# hdmi_block.net
KiCad netlist of a schematic drawn in Altium Designer
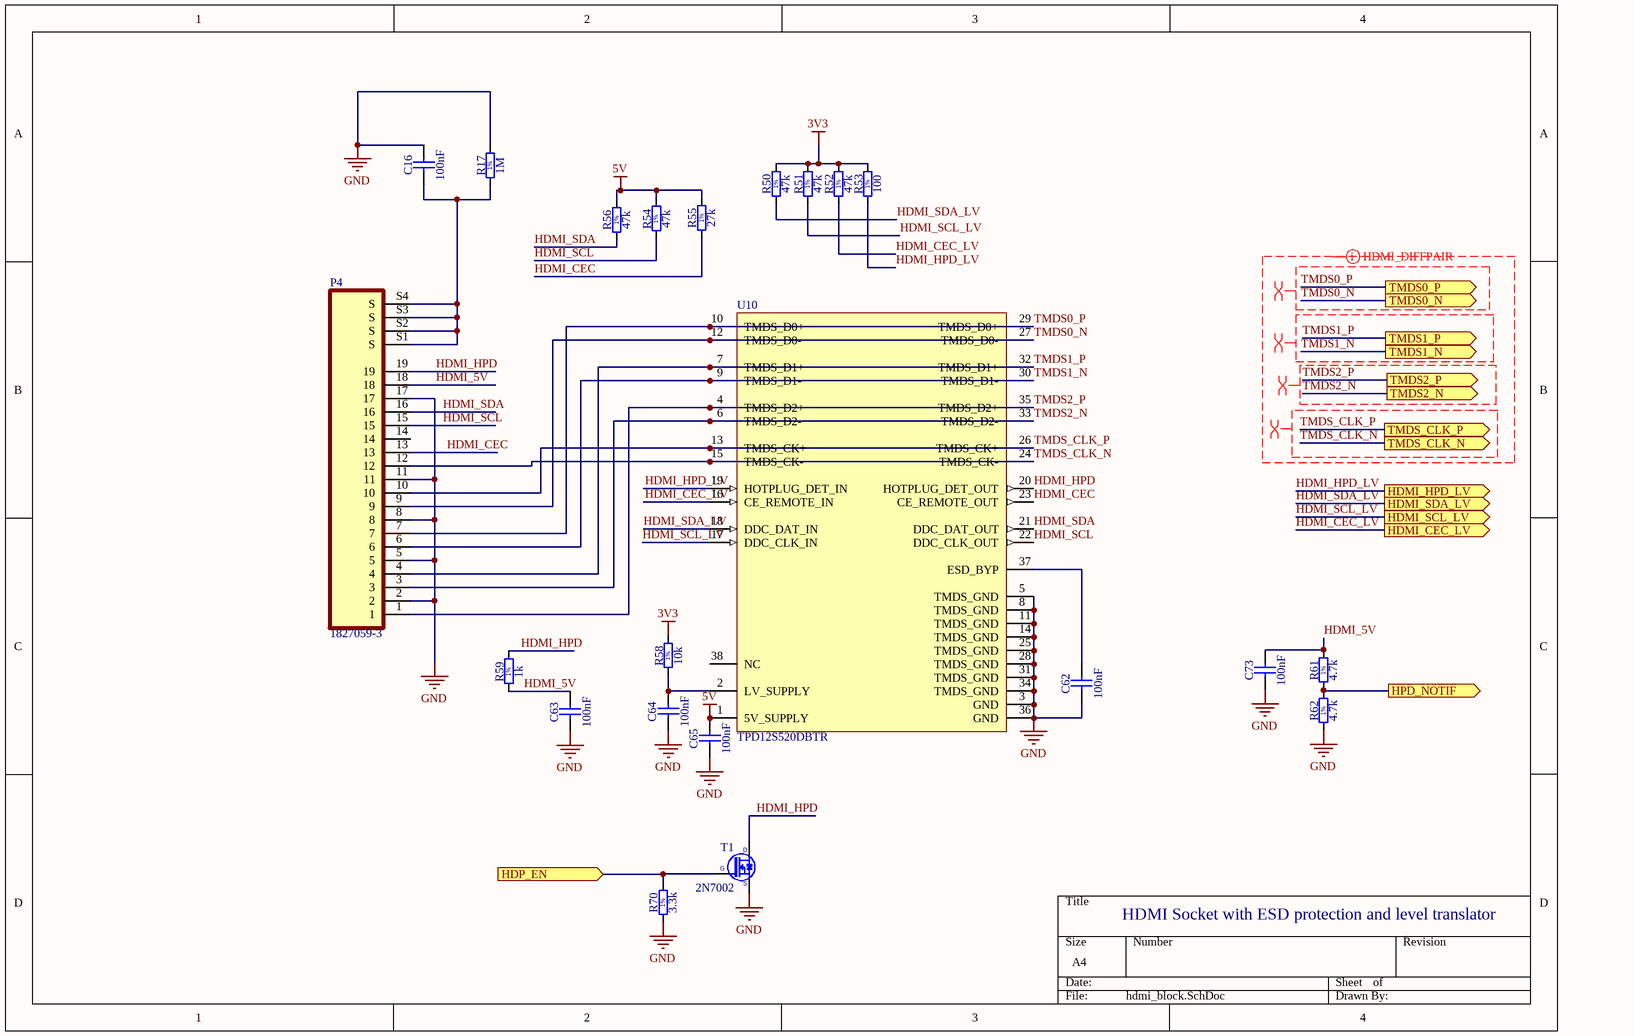
[diagram p0: hdmi_block.SchDoc]

(export (version "E")
  (design (tool "Eeschema 10.0.6"))
  (components
    (comp (ref "C16")
      (value "100nF")
      (footprint "CAPC2013X100N")
      (description "Non-polarised capacitor")
      (fields
        (field (name "PART NUMBER") "CC0805_1.5NF_50V_5%_C0G")
        (field (name "VOLTAGE") "50V")
        (field (name "AUTHOR") "CERN DEM BC")
      )
      (libsource (lib "Capacitors") (part "Capacitor - non polarized"))
    )
    (comp (ref "C62")
      (value "100nF")
      (footprint "CAPC2013X100N")
      (description "Non-polarised capacitor")
      (fields
        (field (name "PART NUMBER") "CC0805_1.5NF_50V_5%_C0G")
        (field (name "VOLTAGE") "50V")
        (field (name "AUTHOR") "CERN DEM BC")
      )
      (libsource (lib "Capacitors") (part "Capacitor - non polarized"))
    )
    (comp (ref "C63")
      (value "100nF")
      (footprint "CAPC2013X100N")
      (description "Non-polarised capacitor")
      (fields
        (field (name "PART NUMBER") "CC0805_1.5NF_50V_5%_C0G")
        (field (name "VOLTAGE") "50V")
        (field (name "AUTHOR") "CERN DEM BC")
      )
      (libsource (lib "Capacitors") (part "Capacitor - non polarized"))
    )
    (comp (ref "C64")
      (value "100nF")
      (footprint "CAPC2013X100N")
      (description "Non-polarised capacitor")
      (fields
        (field (name "PART NUMBER") "CC0805_1.5NF_50V_5%_C0G")
        (field (name "VOLTAGE") "50V")
        (field (name "AUTHOR") "CERN DEM BC")
      )
      (libsource (lib "Capacitors") (part "Capacitor - non polarized"))
    )
    (comp (ref "C65")
      (value "100nF")
      (footprint "CAPC2013X100N")
      (description "Non-polarised capacitor")
      (fields
        (field (name "PART NUMBER") "CC0805_1.5NF_50V_5%_C0G")
        (field (name "VOLTAGE") "50V")
        (field (name "AUTHOR") "CERN DEM BC")
      )
      (libsource (lib "Capacitors") (part "Capacitor - non polarized"))
    )
    (comp (ref "C73")
      (value "100nF")
      (footprint "CAPC2013X100N")
      (description "Non-polarised capacitor")
      (fields
        (field (name "PART NUMBER") "CC0805_1.5NF_50V_5%_C0G")
        (field (name "VOLTAGE") "50V")
        (field (name "AUTHOR") "CERN DEM BC")
      )
      (libsource (lib "Capacitors") (part "Capacitor - non polarized"))
    )
    (comp (ref "P4")
      (value "1827059-3")
      (footprint "TE_1827059-3")
      (description "EMBOSS PACKAGE HDMI CONN SMT NO-FLANGE T")
      (fields (field (name "MF") "TE Connectivity"))
      (libsource (lib "hdmi_conn_1827059-3") (part "1827059-3"))
    )
    (comp (ref "R17")
      (value "1M")
      (footprint "RESC1608X55N")
      (description "Resistor - 1%")
      (fields
        (field (name "PART NUMBER") "R0603_100K_1%_0.1W_100PPM")
        (field (name "POWER") "0.1W")
        (field (name "AUTHOR") "CERN DEM JLC")
      )
      (libsource (lib "Resistors") (part "Resistor - 1%"))
    )
    (comp (ref "R50")
      (value "47k")
      (footprint "RESC1608X55N")
      (description "Resistor - 1%")
      (fields
        (field (name "PART NUMBER") "R0603_100K_1%_0.1W_100PPM")
        (field (name "POWER") "0.1W")
        (field (name "AUTHOR") "CERN DEM JLC")
      )
      (libsource (lib "Resistors") (part "Resistor - 1%"))
    )
    (comp (ref "R51")
      (value "47k")
      (footprint "RESC1608X55N")
      (description "Resistor - 1%")
      (fields
        (field (name "PART NUMBER") "R0603_100K_1%_0.1W_100PPM")
        (field (name "POWER") "0.1W")
        (field (name "AUTHOR") "CERN DEM JLC")
      )
      (libsource (lib "Resistors") (part "Resistor - 1%"))
    )
    (comp (ref "R52")
      (value "47k")
      (footprint "RESC1608X55N")
      (description "Resistor - 1%")
      (fields
        (field (name "PART NUMBER") "R0603_100K_1%_0.1W_100PPM")
        (field (name "POWER") "0.1W")
        (field (name "AUTHOR") "CERN DEM JLC")
      )
      (libsource (lib "Resistors") (part "Resistor - 1%"))
    )
    (comp (ref "R53")
      (value "100")
      (footprint "RESC1608X55N")
      (description "Resistor - 1%")
      (fields
        (field (name "PART NUMBER") "R0603_100K_1%_0.1W_100PPM")
        (field (name "POWER") "0.1W")
        (field (name "AUTHOR") "CERN DEM JLC")
      )
      (libsource (lib "Resistors") (part "Resistor - 1%"))
    )
    (comp (ref "R54")
      (value "47k")
      (footprint "RESC1608X55N")
      (description "Resistor - 1%")
      (fields
        (field (name "PART NUMBER") "R0603_100K_1%_0.1W_100PPM")
        (field (name "POWER") "0.1W")
        (field (name "AUTHOR") "CERN DEM JLC")
      )
      (libsource (lib "Resistors") (part "Resistor - 1%"))
    )
    (comp (ref "R55")
      (value "27k")
      (footprint "RESC1608X55N")
      (description "Resistor - 1%")
      (fields
        (field (name "PART NUMBER") "R0603_100K_1%_0.1W_100PPM")
        (field (name "POWER") "0.1W")
        (field (name "AUTHOR") "CERN DEM JLC")
      )
      (libsource (lib "Resistors") (part "Resistor - 1%"))
    )
    (comp (ref "R56")
      (value "47k")
      (footprint "RESC1608X55N")
      (description "Resistor - 1%")
      (fields
        (field (name "PART NUMBER") "R0603_100K_1%_0.1W_100PPM")
        (field (name "POWER") "0.1W")
        (field (name "AUTHOR") "CERN DEM JLC")
      )
      (libsource (lib "Resistors") (part "Resistor - 1%"))
    )
    (comp (ref "R58")
      (value "10k")
      (footprint "RESC1608X55N")
      (description "Resistor - 1%")
      (fields
        (field (name "PART NUMBER") "R0603_100K_1%_0.1W_100PPM")
        (field (name "POWER") "0.1W")
        (field (name "AUTHOR") "CERN DEM JLC")
      )
      (libsource (lib "Resistors") (part "Resistor - 1%"))
    )
    (comp (ref "R59")
      (value "1k")
      (footprint "RESC1608X55N")
      (description "Resistor - 1%")
      (fields
        (field (name "PART NUMBER") "R0603_100K_1%_0.1W_100PPM")
        (field (name "POWER") "0.1W")
        (field (name "AUTHOR") "CERN DEM JLC")
      )
      (libsource (lib "Resistors") (part "Resistor - 1%"))
    )
    (comp (ref "R61")
      (value "4.7k")
      (footprint "RESC1608X55N")
      (description "Resistor - 1%")
      (fields
        (field (name "PART NUMBER") "R0603_100K_1%_0.1W_100PPM")
        (field (name "POWER") "0.1W")
        (field (name "AUTHOR") "CERN DEM JLC")
      )
      (libsource (lib "Resistors") (part "Resistor - 1%"))
    )
    (comp (ref "R62")
      (value "4.7k")
      (footprint "RESC1608X55N")
      (description "Resistor - 1%")
      (fields
        (field (name "PART NUMBER") "R0603_100K_1%_0.1W_100PPM")
        (field (name "POWER") "0.1W")
        (field (name "AUTHOR") "CERN DEM JLC")
      )
      (libsource (lib "Resistors") (part "Resistor - 1%"))
    )
    (comp (ref "R70")
      (value "3.3k")
      (footprint "RESC1608X55N")
      (description "Resistor - 1%")
      (fields
        (field (name "PART NUMBER") "R0603_100K_1%_0.1W_100PPM")
        (field (name "POWER") "0.1W")
        (field (name "AUTHOR") "CERN DEM JLC")
      )
      (libsource (lib "Resistors") (part "Resistor - 1%"))
    )
    (comp (ref "T1")
      (value "2N7002")
      (footprint "SOT95P240X130-3N")
      (description "N-CHANNEL MOSFET WITH DIODE")
      (fields (field (name "MANUFACTURER") "FAIRCHILD SEMICONDUCTOR") (field (name "AUTHOR") "CERN DEM JLC"))
      (libsource (lib "ICs And Semiconductors") (part "N-MOSFET-D 1G 2S 3D"))
    )
    (comp (ref "U10")
      (value "TPD12S520DBTR")
      (footprint "DBT38_L")
      (fields (field (name "MANUFACTURER") "Texas Instruments"))
      (libsource (lib "TI Interface ESD EMI Protection") (part "TPD12S520DBTR"))
    )
  )
  (nets
    (net (code "1") (name "/HDMI_5V") (class "Default")
      (node (ref "C63") (pin "2") (pinfunction "2_2") (pintype "passive"))
      (node (ref "C73") (pin "2") (pinfunction "2_2") (pintype "passive"))
      (node (ref "P4") (pin "18") (pinfunction "18_18") (pintype "passive"))
      (node (ref "R59") (pin "1") (pinfunction "1_1") (pintype "passive"))
      (node (ref "R61") (pin "2") (pinfunction "2_2") (pintype "passive"))
    )
    (net (code "2") (name "/HDMI_CEC") (class "Default")
      (node (ref "P4") (pin "13") (pinfunction "13_13") (pintype "passive"))
      (node (ref "R55") (pin "1") (pinfunction "1_1") (pintype "passive"))
      (node (ref "U10") (pin "23") (pinfunction "CE_REMOTE_OUT_23") (pintype "output"))
    )
    (net (code "3") (name "/HDMI_CEC_LV") (class "Default")
      (node (ref "R52") (pin "1") (pinfunction "1_1") (pintype "passive"))
      (node (ref "U10") (pin "16") (pinfunction "CE_REMOTE_IN_16") (pintype "input"))
    )
    (net (code "4") (name "/HDMI_HPD") (class "Default")
      (node (ref "P4") (pin "19") (pinfunction "19_19") (pintype "passive"))
      (node (ref "R59") (pin "2") (pinfunction "2_2") (pintype "passive"))
      (node (ref "T1") (pin "3") (pinfunction "D_3") (pintype "passive"))
      (node (ref "U10") (pin "20") (pinfunction "HOTPLUG_DET_OUT_20") (pintype "output"))
    )
    (net (code "5") (name "/HDMI_HPD_LV") (class "Default")
      (node (ref "R53") (pin "1") (pinfunction "1_1") (pintype "passive"))
      (node (ref "U10") (pin "19") (pinfunction "HOTPLUG_DET_IN_19") (pintype "input"))
    )
    (net (code "6") (name "/HDMI_SCL") (class "Default")
      (node (ref "P4") (pin "15") (pinfunction "15_15") (pintype "passive"))
      (node (ref "R54") (pin "1") (pinfunction "1_1") (pintype "passive"))
      (node (ref "U10") (pin "22") (pinfunction "DDC_CLK_OUT_22") (pintype "output"))
    )
    (net (code "7") (name "/HDMI_SCL_LV") (class "Default")
      (node (ref "R51") (pin "1") (pinfunction "1_1") (pintype "passive"))
      (node (ref "U10") (pin "17") (pinfunction "DDC_CLK_IN_17") (pintype "input"))
    )
    (net (code "8") (name "/HDMI_SDA") (class "Default")
      (node (ref "P4") (pin "16") (pinfunction "16_16") (pintype "passive"))
      (node (ref "R56") (pin "1") (pinfunction "1_1") (pintype "passive"))
      (node (ref "U10") (pin "21") (pinfunction "DDC_DAT_OUT_21") (pintype "output"))
    )
    (net (code "9") (name "/HDMI_SDA_LV") (class "Default")
      (node (ref "R50") (pin "1") (pinfunction "1_1") (pintype "passive"))
      (node (ref "U10") (pin "18") (pinfunction "DDC_DAT_IN_18") (pintype "input"))
    )
    (net (code "10") (name "/HDP_EN") (class "Default")
      (node (ref "R70") (pin "2") (pinfunction "2_2") (pintype "passive"))
      (node (ref "T1") (pin "1") (pinfunction "G_1") (pintype "passive"))
    )
    (net (code "11") (name "/HPD_NOTIF") (class "Default")
      (node (ref "R61") (pin "1") (pinfunction "1_1") (pintype "passive"))
      (node (ref "R62") (pin "2") (pinfunction "2_2") (pintype "passive"))
    )
    (net (code "12") (name "/TMDS0_N") (class "Default")
      (node (ref "P4") (pin "9") (pinfunction "9_9") (pintype "passive"))
      (node (ref "U10") (pin "12") (pinfunction "TMDS_D0-_12") (pintype "passive"))
      (node (ref "U10") (pin "27") (pinfunction "TMDS_D0-_27") (pintype "passive"))
    )
    (net (code "13") (name "/TMDS0_P") (class "Default")
      (node (ref "P4") (pin "7") (pinfunction "7_7") (pintype "passive"))
      (node (ref "U10") (pin "10") (pinfunction "TMDS_D0+_10") (pintype "passive"))
      (node (ref "U10") (pin "29") (pinfunction "TMDS_D0+_29") (pintype "passive"))
    )
    (net (code "14") (name "/TMDS1_N") (class "Default")
      (node (ref "P4") (pin "6") (pinfunction "6_6") (pintype "passive"))
      (node (ref "U10") (pin "30") (pinfunction "TMDS_D1-_30") (pintype "passive"))
      (node (ref "U10") (pin "9") (pinfunction "TMDS_D1-_9") (pintype "passive"))
    )
    (net (code "15") (name "/TMDS1_P") (class "Default")
      (node (ref "P4") (pin "4") (pinfunction "4_4") (pintype "passive"))
      (node (ref "U10") (pin "32") (pinfunction "TMDS_D1+_32") (pintype "passive"))
      (node (ref "U10") (pin "7") (pinfunction "TMDS_D1+_7") (pintype "passive"))
    )
    (net (code "16") (name "/TMDS2_N") (class "Default")
      (node (ref "P4") (pin "3") (pinfunction "3_3") (pintype "passive"))
      (node (ref "U10") (pin "33") (pinfunction "TMDS_D2-_33") (pintype "passive"))
      (node (ref "U10") (pin "6") (pinfunction "TMDS_D2-_6") (pintype "passive"))
    )
    (net (code "17") (name "/TMDS2_P") (class "Default")
      (node (ref "P4") (pin "1") (pinfunction "1_1") (pintype "passive"))
      (node (ref "U10") (pin "35") (pinfunction "TMDS_D2+_35") (pintype "passive"))
      (node (ref "U10") (pin "4") (pinfunction "TMDS_D2+_4") (pintype "passive"))
    )
    (net (code "18") (name "/TMDS_CLK_N") (class "Default")
      (node (ref "P4") (pin "12") (pinfunction "12_12") (pintype "passive"))
      (node (ref "U10") (pin "15") (pinfunction "TMDS_CK-_15") (pintype "passive"))
      (node (ref "U10") (pin "24") (pinfunction "TMDS_CK-_24") (pintype "passive"))
    )
    (net (code "19") (name "/TMDS_CLK_P") (class "Default")
      (node (ref "P4") (pin "10") (pinfunction "10_10") (pintype "passive"))
      (node (ref "U10") (pin "13") (pinfunction "TMDS_CK+_13") (pintype "passive"))
      (node (ref "U10") (pin "26") (pinfunction "TMDS_CK+_26") (pintype "passive"))
    )
    (net (code "20") (name "3V3") (class "Default")
      (node (ref "R50") (pin "2") (pinfunction "2_2") (pintype "passive"))
      (node (ref "R51") (pin "2") (pinfunction "2_2") (pintype "passive"))
      (node (ref "R52") (pin "2") (pinfunction "2_2") (pintype "passive"))
      (node (ref "R53") (pin "2") (pinfunction "2_2") (pintype "passive"))
      (node (ref "R58") (pin "2") (pinfunction "2_2") (pintype "passive"))
    )
    (net (code "21") (name "5V") (class "Default")
      (node (ref "C65") (pin "2") (pinfunction "2_2") (pintype "passive"))
      (node (ref "R54") (pin "2") (pinfunction "2_2") (pintype "passive"))
      (node (ref "R55") (pin "2") (pinfunction "2_2") (pintype "passive"))
      (node (ref "R56") (pin "2") (pinfunction "2_2") (pintype "passive"))
      (node (ref "U10") (pin "1") (pinfunction "5V_SUPPLY_1") (pintype "power_in"))
    )
    (net (code "22") (name "GND") (class "Default")
      (node (ref "C16") (pin "2") (pinfunction "2_2") (pintype "passive"))
      (node (ref "C62") (pin "1") (pinfunction "1_1") (pintype "passive"))
      (node (ref "C63") (pin "1") (pinfunction "1_1") (pintype "passive"))
      (node (ref "C64") (pin "1") (pinfunction "1_1") (pintype "passive"))
      (node (ref "C65") (pin "1") (pinfunction "1_1") (pintype "passive"))
      (node (ref "C73") (pin "1") (pinfunction "1_1") (pintype "passive"))
      (node (ref "P4") (pin "11") (pinfunction "11_11") (pintype "passive"))
      (node (ref "P4") (pin "17") (pinfunction "17_17") (pintype "passive"))
      (node (ref "P4") (pin "2") (pinfunction "2_2") (pintype "passive"))
      (node (ref "P4") (pin "5") (pinfunction "5_5") (pintype "passive"))
      (node (ref "P4") (pin "8") (pinfunction "8_8") (pintype "passive"))
      (node (ref "R17") (pin "2") (pinfunction "2_2") (pintype "passive"))
      (node (ref "R62") (pin "1") (pinfunction "1_1") (pintype "passive"))
      (node (ref "R70") (pin "1") (pinfunction "1_1") (pintype "passive"))
      (node (ref "T1") (pin "2") (pinfunction "S_2") (pintype "passive"))
      (node (ref "U10") (pin "11") (pinfunction "TMDS_GND_11") (pintype "power_in"))
      (node (ref "U10") (pin "14") (pinfunction "TMDS_GND_14") (pintype "power_in"))
      (node (ref "U10") (pin "25") (pinfunction "TMDS_GND_25") (pintype "power_in"))
      (node (ref "U10") (pin "28") (pinfunction "TMDS_GND_28") (pintype "power_in"))
      (node (ref "U10") (pin "3") (pinfunction "GND_3") (pintype "power_in"))
      (node (ref "U10") (pin "31") (pinfunction "TMDS_GND_31") (pintype "power_in"))
      (node (ref "U10") (pin "34") (pinfunction "TMDS_GND_34") (pintype "power_in"))
      (node (ref "U10") (pin "36") (pinfunction "GND_36") (pintype "power_in"))
      (node (ref "U10") (pin "5") (pinfunction "TMDS_GND_5") (pintype "power_in"))
      (node (ref "U10") (pin "8") (pinfunction "TMDS_GND_8") (pintype "power_in"))
    )
    (net (code "23") (name "Net-(C16-Pad1)") (class "Default")
      (node (ref "C16") (pin "1") (pinfunction "1_1") (pintype "passive"))
      (node (ref "P4") (pin "S1") (pinfunction "S_S1") (pintype "passive"))
      (node (ref "P4") (pin "S2") (pinfunction "S_S2") (pintype "passive"))
      (node (ref "P4") (pin "S3") (pinfunction "S_S3") (pintype "passive"))
      (node (ref "P4") (pin "S4") (pinfunction "S_S4") (pintype "passive"))
      (node (ref "R17") (pin "1") (pinfunction "1_1") (pintype "passive"))
    )
    (net (code "24") (name "Net-(U10-ESD_BYP)") (class "Default")
      (node (ref "C62") (pin "2") (pinfunction "2_2") (pintype "passive"))
      (node (ref "U10") (pin "37") (pinfunction "ESD_BYP_37") (pintype "passive"))
    )
    (net (code "25") (name "Net-(U10-LV_SUPPLY)") (class "Default")
      (node (ref "C64") (pin "2") (pinfunction "2_2") (pintype "passive"))
      (node (ref "R58") (pin "1") (pinfunction "1_1") (pintype "passive"))
      (node (ref "U10") (pin "2") (pinfunction "LV_SUPPLY_2") (pintype "passive"))
    )
    (net (code "26") (name "unconnected-(P4-Pad14)") (class "Default")
      (node (ref "P4") (pin "14") (pinfunction "14_14") (pintype "passive"))
    )
    (net (code "27") (name "unconnected-(U10-NC-Pad38)") (class "Default")
      (node (ref "U10") (pin "38") (pinfunction "NC_38") (pintype "passive"))
    )
  )
)
